# DCDC_12V_5V_3_3V.net
KiCad netlist of a schematic drawn in Altium Designer
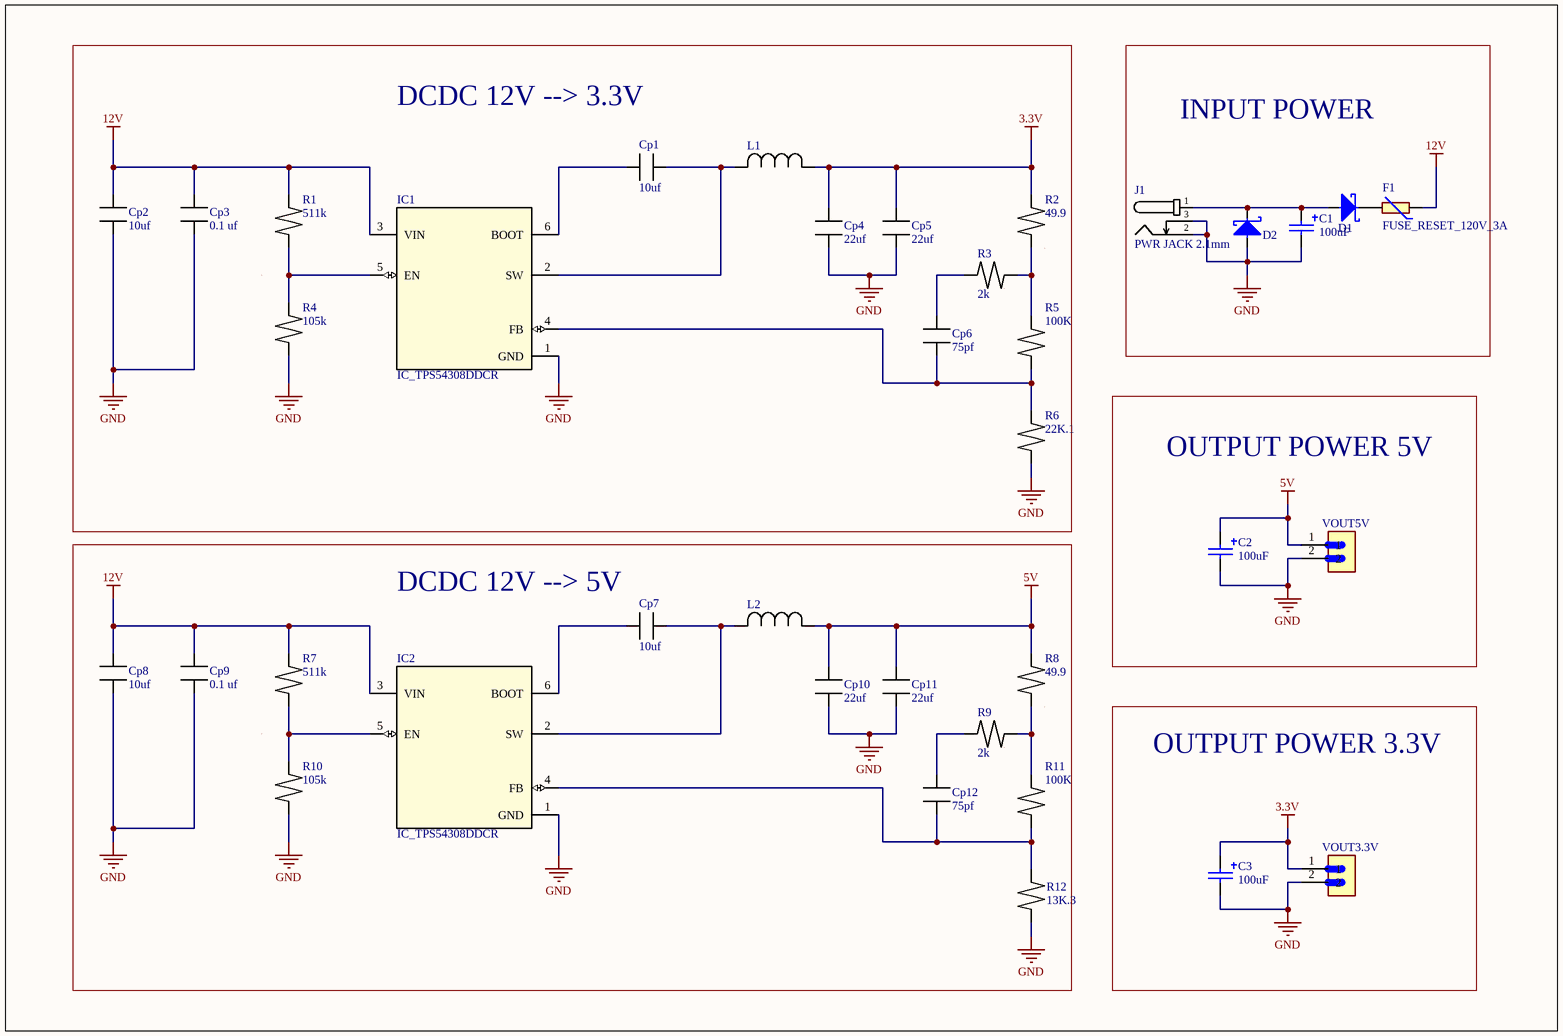
[diagram p0: DCDC_12V_5V_3.3V.SchDoc]

(export (version "E")
  (design (tool "Eeschema 10.0.6"))
  (components
    (comp (ref "C1")
      (value "100uF")
      (footprint "CAP_TH_2.5MM_6.3*12MM")
      (description "100uF 35V ±20% Plugin,D6.3xL12mm Aluminum Electrolytic Capacitors - Leaded ROHS")
      (fields (field (name "MANUFACTURER") "HRK") (field (name "MANUFACTURER PART NUMBER") "35V100uF CD110"))
      (libsource (lib "shared_lib") (part "Cap_100uF_ALU_TH_35V"))
    )
    (comp (ref "C2")
      (value "100uF")
      (footprint "CAP_TH_2.5MM_6.3*12MM")
      (description "100uF 35V ±20% Plugin,D6.3xL12mm Aluminum Electrolytic Capacitors - Leaded ROHS")
      (fields (field (name "MANUFACTURER") "HRK") (field (name "MANUFACTURER PART NUMBER") "35V100uF CD110"))
      (libsource (lib "shared_lib") (part "Cap_100uF_ALU_TH_35V"))
    )
    (comp (ref "C3")
      (value "100uF")
      (footprint "CAP_TH_2.5MM_6.3*12MM")
      (description "100uF 35V ±20% Plugin,D6.3xL12mm Aluminum Electrolytic Capacitors - Leaded ROHS")
      (fields (field (name "MANUFACTURER") "HRK") (field (name "MANUFACTURER PART NUMBER") "35V100uF CD110"))
      (libsource (lib "shared_lib") (part "Cap_100uF_ALU_TH_35V"))
    )
    (comp (ref "Cp1")
      (value "10uf")
      (footprint "Capacitor_0805")
      (description "CAP CER 10UF 50V X5R 0805")
      (fields (field (name "MANUFACTURER") "Murata Electronics") (field (name "Comment") "10uf 0805"))
      (libsource (lib "Schlib1") (part "Capacitor_10uf_0805_50V"))
    )
    (comp (ref "Cp2")
      (value "10uf")
      (footprint "Capacitor_0805")
      (description "CAP CER 10UF 50V X5R 0805")
      (fields (field (name "MANUFACTURER") "Murata Electronics") (field (name "Comment") "10uf 0805"))
      (libsource (lib "Schlib1") (part "Capacitor_10uf_0805_50V"))
    )
    (comp (ref "Cp3")
      (value "0.1 uf")
      (footprint "Capacitor_0603")
      (description "CAP CER 0.1UF 50V X7R 0603")
      (fields (field (name "MANUFACTURER") "KYOCERA AVX") (field (name "Comment") "0.1uf 0603"))
      (libsource (lib "Schlib1") (part "Capacitor_0.1uf_0603_50V"))
    )
    (comp (ref "Cp4")
      (value "22uf")
      (footprint "Capacitor_0805")
      (description "CAP0805 X5R 22UF 20% 25V")
      (fields (field (name "MANUFACTURER") "Cal-Chip Electronics, Inc.") (field (name "Comment") "22uf 0805"))
      (libsource (lib "Schlib1") (part "Capacitor_22uf_0805_50V_1"))
    )
    (comp (ref "Cp5")
      (value "22uf")
      (footprint "Capacitor_0805")
      (description "CAP0805 X5R 22UF 20% 25V")
      (fields (field (name "MANUFACTURER") "Cal-Chip Electronics, Inc.") (field (name "Comment") "22uf 0805"))
      (libsource (lib "Schlib1") (part "Capacitor_22uf_0805_50V_1"))
    )
    (comp (ref "Cp6")
      (value "75pf")
      (footprint "Capacitor_0805")
      (description "CAP CER 75PF 50V C0G/NPO 0805")
      (fields (field (name "MANUFACTURER") "YAGEO") (field (name "Comment") "75pf 0805"))
      (libsource (lib "Schlib1") (part "Capacitor_75pf_0805_50V"))
    )
    (comp (ref "Cp7")
      (value "10uf")
      (footprint "Capacitor_0805")
      (description "CAP CER 10UF 50V X5R 0805")
      (fields (field (name "MANUFACTURER") "Murata Electronics") (field (name "Comment") "10uf 0805"))
      (libsource (lib "Schlib1") (part "Capacitor_10uf_0805_50V"))
    )
    (comp (ref "Cp8")
      (value "10uf")
      (footprint "Capacitor_0805")
      (description "CAP CER 10UF 50V X5R 0805")
      (fields (field (name "MANUFACTURER") "Murata Electronics") (field (name "Comment") "10uf 0805"))
      (libsource (lib "Schlib1") (part "Capacitor_10uf_0805_50V"))
    )
    (comp (ref "Cp9")
      (value "0.1 uf")
      (footprint "Capacitor_0603")
      (description "CAP CER 0.1UF 50V X7R 0603")
      (fields (field (name "MANUFACTURER") "KYOCERA AVX") (field (name "Comment") "0.1uf 0603"))
      (libsource (lib "Schlib1") (part "Capacitor_0.1uf_0603_50V"))
    )
    (comp (ref "Cp10")
      (value "22uf")
      (footprint "Capacitor_0805")
      (description "CAP0805 X5R 22UF 20% 25V")
      (fields (field (name "MANUFACTURER") "Cal-Chip Electronics, Inc.") (field (name "Comment") "22uf 0805"))
      (libsource (lib "Schlib1") (part "Capacitor_22uf_0805_50V_1"))
    )
    (comp (ref "Cp11")
      (value "22uf")
      (footprint "Capacitor_0805")
      (description "CAP0805 X5R 22UF 20% 25V")
      (fields (field (name "MANUFACTURER") "Cal-Chip Electronics, Inc.") (field (name "Comment") "22uf 0805"))
      (libsource (lib "Schlib1") (part "Capacitor_22uf_0805_50V_1"))
    )
    (comp (ref "Cp12")
      (value "75pf")
      (footprint "Capacitor_0805")
      (description "CAP CER 75PF 50V C0G/NPO 0805")
      (fields (field (name "MANUFACTURER") "YAGEO") (field (name "Comment") "75pf 0805"))
      (libsource (lib "Schlib1") (part "Capacitor_75pf_0805_50V"))
    )
    (comp (ref "D1")
      (value "30V 3A")
      (footprint "SMA")
      (description "40V Independent 3A 550mV@3A SMA Schottky Diodes ROHS")
      (fields (field (name "MANUFACTURER") "TDSEMIC") (field (name "MANUFACTURER PART NUMBER") "SS34-TD"))
      (libsource (lib "shared_lib") (part "D_Schottky_40V_3A_SMA"))
    )
    (comp (ref "D2")
      (value "30V 3A")
      (footprint "SMA")
      (description "40V Independent 3A 550mV@3A SMA Schottky Diodes ROHS")
      (fields (field (name "MANUFACTURER") "TDSEMIC") (field (name "MANUFACTURER PART NUMBER") "SS34-TD"))
      (libsource (lib "shared_lib") (part "D_Schottky_40V_3A_SMA"))
    )
    (comp (ref "F1")
      (value "FUSE_RESET_120V_3A")
      (footprint "FUS_RES_120V_3A")
      (description "PTC RESET FUSE 120V 300MA RADIAL")
      (fields (field (name "MANUFACTURER") "Bel Fuse Inc."))
      (libsource (lib "Schlib1") (part "FUSE_RESET_120V_3A"))
    )
    (comp (ref "IC1")
      (value "IC_TPS54308DDCR")
      (footprint "IC_TPS54308DDCR")
      (description "IC REG BUCK ADJ 3A SOT23")
      (fields (field (name "MANUFACTURER") "Texas Instruments"))
      (libsource (lib "Schlib1") (part "IC_TPS54308DDCR"))
    )
    (comp (ref "IC2")
      (value "IC_TPS54308DDCR")
      (footprint "IC_TPS54308DDCR")
      (description "IC REG BUCK ADJ 3A SOT23")
      (fields (field (name "MANUFACTURER") "Texas Instruments"))
      (libsource (lib "Schlib1") (part "IC_TPS54308DDCR"))
    )
    (comp (ref "J1")
      (value "PWR JACK 2.1mm")
      (footprint "CON_POWER_BARREL_2.1MM_3CONN")
      (description "CONN PWR JACK 2X5.5MM SOLDER")
      (fields (field (name "MANUFACTURER") "HCTL") (field (name "MANUFACTURER PART NUMBER") "HC-DC-005-2.0T"))
      (libsource (lib "shared_lib") (part "Con_Power_Jack_2.1mm_3pins"))
    )
    (comp (ref "L1")
      (value "IND 10UH 3.1A")
      (footprint "Inductor_10uh_3.1A")
      (description "FIXED IND 10UH 3.1A 44.2 MOHM")
      (fields (field (name "MANUFACTURER") "Taiyo Yuden"))
      (libsource (lib "Schlib1") (part "IND_10UH_3.1A"))
    )
    (comp (ref "L2")
      (value "IND 15UH 3.1A")
      (footprint "Inductor_10uh_3.1A")
      (description "FIXED IND 15UH 3.1A 44 MOHM SMD")
      (fields (field (name "MANUFACTURER") "Eaton - Electronics Division"))
      (libsource (lib "Schlib1") (part "IND_15UH_3.1A"))
    )
    (comp (ref "R1")
      (value "511k")
      (footprint "0603_resistor")
      (description "RES 511K OHM 1% 1/10W 0603")
      (fields (field (name "MANUFACTURER") "Cal-Chip Electronics, Inc.") (field (name "Comment") "511K 0603"))
      (libsource (lib "Schlib1") (part "RES_511K_0603_1/10W_1%_1_1_1"))
    )
    (comp (ref "R2")
      (value "49.9")
      (footprint "0603_resistor")
      (description "RES 49.9 OHM 1% 1/10W 0603")
      (fields (field (name "MANUFACTURER") "YAGEO") (field (name "Comment") "49.9 0603"))
      (libsource (lib "Schlib1") (part "RES_49.9_0603_1/10W_1%"))
    )
    (comp (ref "R3")
      (value "2k")
      (footprint "0603_resistor")
      (description "RES 2K OHM 1% 1/10W 0603")
      (fields (field (name "MANUFACTURER") "NIC Components Corp") (field (name "Comment") "2K 0603"))
      (libsource (lib "Schlib1") (part "RES_2K_0603_1/10W_1%_1"))
    )
    (comp (ref "R4")
      (value "105k")
      (footprint "0603_resistor")
      (description "RES 105K OHM 1% 1/10W 0603")
      (fields (field (name "MANUFACTURER") "Cal-Chip Electronics, Inc.") (field (name "Comment") "105K 0603"))
      (libsource (lib "Schlib1") (part "RES_105K_0603_1/10W_1%_1_1"))
    )
    (comp (ref "R5")
      (value "100K")
      (footprint "0603_resistor")
      (description "RES 100K OHM 1% 1/10W 0603")
      (fields (field (name "MANUFACTURER") "YAGEO") (field (name "Comment") "100K 0603"))
      (libsource (lib "Schlib1") (part "RES_100K_0603_1/10W_1%_1"))
    )
    (comp (ref "R6")
      (value "22K.1")
      (footprint "0603_resistor")
      (description "RES 22K.1 OHM 1% 1/10W 0603")
      (fields (field (name "MANUFACTURER") "YAGEO") (field (name "Comment") "22K.1 0603"))
      (libsource (lib "Schlib1") (part "RES_22K.1_0603_1/10W_1%_1_1"))
    )
    (comp (ref "R7")
      (value "511k")
      (footprint "0603_resistor")
      (description "RES 511K OHM 1% 1/10W 0603")
      (fields (field (name "MANUFACTURER") "Cal-Chip Electronics, Inc.") (field (name "Comment") "511K 0603"))
      (libsource (lib "Schlib1") (part "RES_511K_0603_1/10W_1%_1_1_1"))
    )
    (comp (ref "R8")
      (value "49.9")
      (footprint "0603_resistor")
      (description "RES 49.9 OHM 1% 1/10W 0603")
      (fields (field (name "MANUFACTURER") "YAGEO") (field (name "Comment") "49.9 0603"))
      (libsource (lib "Schlib1") (part "RES_49.9_0603_1/10W_1%"))
    )
    (comp (ref "R9")
      (value "2k")
      (footprint "0603_resistor")
      (description "RES 2K OHM 1% 1/10W 0603")
      (fields (field (name "MANUFACTURER") "NIC Components Corp") (field (name "Comment") "2K 0603"))
      (libsource (lib "Schlib1") (part "RES_2K_0603_1/10W_1%_1"))
    )
    (comp (ref "R10")
      (value "105k")
      (footprint "0603_resistor")
      (description "RES 105K OHM 1% 1/10W 0603")
      (fields (field (name "MANUFACTURER") "Cal-Chip Electronics, Inc.") (field (name "Comment") "105K 0603"))
      (libsource (lib "Schlib1") (part "RES_105K_0603_1/10W_1%_1_1"))
    )
    (comp (ref "R11")
      (value "100K")
      (footprint "0603_resistor")
      (description "RES 100K OHM 1% 1/10W 0603")
      (fields (field (name "MANUFACTURER") "YAGEO") (field (name "Comment") "100K 0603"))
      (libsource (lib "Schlib1") (part "RES_100K_0603_1/10W_1%_1"))
    )
    (comp (ref "R12")
      (value "13K.3")
      (footprint "0603_resistor")
      (description "RES 13.3K OHM 1% 1/10W 0603")
      (fields (field (name "MANUFACTURER") "Stackpole Electronics Inc") (field (name "Comment") "13K.3 0603"))
      (libsource (lib "Schlib1") (part "RES_13K.3_0603_1/10W_1%_"))
    )
    (comp (ref "VOUT3.3V")
      (value "TERM BLK 2POS")
      (footprint "TERM_BLK_2POS")
      (description "TERM BLK 2POS SIDE ENT 3.5MM PCB")
      (fields (field (name "MANUFACTURER") "On Shore Technology Inc."))
      (libsource (lib "Schlib1") (part "TERM_BLK_2POS"))
    )
    (comp (ref "VOUT5V")
      (value "TERM BLK 2POS")
      (footprint "TERM_BLK_2POS")
      (description "TERM BLK 2POS SIDE ENT 3.5MM PCB")
      (fields (field (name "MANUFACTURER") "On Shore Technology Inc."))
      (libsource (lib "Schlib1") (part "TERM_BLK_2POS"))
    )
  )
  (nets
    (net (code "1") (name "3.3V") (class "Default")
      (node (ref "C3") (pin "1") (pinfunction "1_1") (pintype "passive"))
      (node (ref "Cp4") (pin "2") (pinfunction "-_2") (pintype "passive"))
      (node (ref "Cp5") (pin "2") (pinfunction "-_2") (pintype "passive"))
      (node (ref "L1") (pin "1") (pinfunction "1_1") (pintype "passive"))
      (node (ref "R2") (pin "2") (pintype "passive"))
      (node (ref "VOUT3.3V") (pin "1") (pinfunction "1_1") (pintype "passive"))
    )
    (net (code "2") (name "5V") (class "Default")
      (node (ref "C2") (pin "1") (pinfunction "1_1") (pintype "passive"))
      (node (ref "Cp10") (pin "2") (pinfunction "-_2") (pintype "passive"))
      (node (ref "Cp11") (pin "2") (pinfunction "-_2") (pintype "passive"))
      (node (ref "L2") (pin "1") (pinfunction "1_1") (pintype "passive"))
      (node (ref "R8") (pin "2") (pintype "passive"))
      (node (ref "VOUT5V") (pin "1") (pinfunction "1_1") (pintype "passive"))
    )
    (net (code "3") (name "12V") (class "Default")
      (node (ref "Cp2") (pin "2") (pinfunction "-_2") (pintype "passive"))
      (node (ref "Cp3") (pin "2") (pinfunction "-_2") (pintype "passive"))
      (node (ref "Cp8") (pin "2") (pinfunction "-_2") (pintype "passive"))
      (node (ref "Cp9") (pin "2") (pinfunction "-_2") (pintype "passive"))
      (node (ref "F1") (pin "1") (pinfunction "1_1") (pintype "passive"))
      (node (ref "IC1") (pin "3") (pinfunction "VIN_3") (pintype "power_in"))
      (node (ref "IC2") (pin "3") (pinfunction "VIN_3") (pintype "power_in"))
      (node (ref "R1") (pin "2") (pintype "passive"))
      (node (ref "R7") (pin "2") (pintype "passive"))
    )
    (net (code "4") (name "GND") (class "Default")
      (node (ref "C1") (pin "2") (pinfunction "2_2") (pintype "passive"))
      (node (ref "C2") (pin "2") (pinfunction "2_2") (pintype "passive"))
      (node (ref "C3") (pin "2") (pinfunction "2_2") (pintype "passive"))
      (node (ref "Cp10") (pin "1") (pinfunction "+_1") (pintype "passive"))
      (node (ref "Cp11") (pin "1") (pinfunction "+_1") (pintype "passive"))
      (node (ref "Cp2") (pin "1") (pinfunction "+_1") (pintype "passive"))
      (node (ref "Cp3") (pin "1") (pinfunction "+_1") (pintype "passive"))
      (node (ref "Cp4") (pin "1") (pinfunction "+_1") (pintype "passive"))
      (node (ref "Cp5") (pin "1") (pinfunction "+_1") (pintype "passive"))
      (node (ref "Cp8") (pin "1") (pinfunction "+_1") (pintype "passive"))
      (node (ref "Cp9") (pin "1") (pinfunction "+_1") (pintype "passive"))
      (node (ref "D2") (pin "2") (pinfunction "2_2") (pintype "passive"))
      (node (ref "IC1") (pin "1") (pinfunction "GND_1") (pintype "power_in"))
      (node (ref "IC2") (pin "1") (pinfunction "GND_1") (pintype "power_in"))
      (node (ref "J1") (pin "2") (pinfunction "2_2") (pintype "passive"))
      (node (ref "J1") (pin "3") (pinfunction "3_3") (pintype "passive"))
      (node (ref "R10") (pin "1") (pintype "passive"))
      (node (ref "R12") (pin "1") (pintype "passive"))
      (node (ref "R4") (pin "1") (pintype "passive"))
      (node (ref "R6") (pin "1") (pintype "passive"))
      (node (ref "VOUT3.3V") (pin "2") (pinfunction "2_2") (pintype "passive"))
      (node (ref "VOUT5V") (pin "2") (pinfunction "2_2") (pintype "passive"))
    )
    (net (code "5") (name "Net-(C1-Pad1)") (class "Default")
      (node (ref "C1") (pin "1") (pinfunction "1_1") (pintype "passive"))
      (node (ref "D1") (pin "2") (pinfunction "2_2") (pintype "passive"))
      (node (ref "D2") (pin "1") (pinfunction "1_1") (pintype "passive"))
      (node (ref "J1") (pin "1") (pinfunction "1_1") (pintype "passive"))
    )
    (net (code "6") (name "Net-(Cp1-+)") (class "Default")
      (node (ref "Cp1") (pin "1") (pinfunction "+_1") (pintype "passive"))
      (node (ref "IC1") (pin "6") (pinfunction "BOOT_6") (pintype "power_in"))
    )
    (net (code "7") (name "Net-(Cp1--)") (class "Default")
      (node (ref "Cp1") (pin "2") (pinfunction "-_2") (pintype "passive"))
      (node (ref "IC1") (pin "2") (pinfunction "SW_2") (pintype "power_in"))
      (node (ref "L1") (pin "2") (pinfunction "2_2") (pintype "passive"))
    )
    (net (code "8") (name "Net-(Cp6-+)") (class "Default")
      (node (ref "Cp6") (pin "1") (pinfunction "+_1") (pintype "passive"))
      (node (ref "IC1") (pin "4") (pinfunction "FB_4") (pintype "bidirectional"))
      (node (ref "R5") (pin "1") (pintype "passive"))
      (node (ref "R6") (pin "2") (pintype "passive"))
    )
    (net (code "9") (name "Net-(Cp6--)") (class "Default")
      (node (ref "Cp6") (pin "2") (pinfunction "-_2") (pintype "passive"))
      (node (ref "R3") (pin "1") (pintype "passive"))
    )
    (net (code "10") (name "Net-(Cp7-+)") (class "Default")
      (node (ref "Cp7") (pin "1") (pinfunction "+_1") (pintype "passive"))
      (node (ref "IC2") (pin "6") (pinfunction "BOOT_6") (pintype "power_in"))
    )
    (net (code "11") (name "Net-(Cp7--)") (class "Default")
      (node (ref "Cp7") (pin "2") (pinfunction "-_2") (pintype "passive"))
      (node (ref "IC2") (pin "2") (pinfunction "SW_2") (pintype "power_in"))
      (node (ref "L2") (pin "2") (pinfunction "2_2") (pintype "passive"))
    )
    (net (code "12") (name "Net-(Cp12-+)") (class "Default")
      (node (ref "Cp12") (pin "1") (pinfunction "+_1") (pintype "passive"))
      (node (ref "IC2") (pin "4") (pinfunction "FB_4") (pintype "bidirectional"))
      (node (ref "R11") (pin "1") (pintype "passive"))
      (node (ref "R12") (pin "2") (pintype "passive"))
    )
    (net (code "13") (name "Net-(Cp12--)") (class "Default")
      (node (ref "Cp12") (pin "2") (pinfunction "-_2") (pintype "passive"))
      (node (ref "R9") (pin "1") (pintype "passive"))
    )
    (net (code "14") (name "Net-(D1-Pad1)") (class "Default")
      (node (ref "D1") (pin "1") (pinfunction "1_1") (pintype "passive"))
      (node (ref "F1") (pin "2") (pinfunction "2_2") (pintype "passive"))
    )
    (net (code "15") (name "Net-(IC1-EN)") (class "Default")
      (node (ref "IC1") (pin "5") (pinfunction "EN_5") (pintype "bidirectional"))
      (node (ref "R1") (pin "1") (pintype "passive"))
      (node (ref "R4") (pin "2") (pintype "passive"))
    )
    (net (code "16") (name "Net-(IC2-EN)") (class "Default")
      (node (ref "IC2") (pin "5") (pinfunction "EN_5") (pintype "bidirectional"))
      (node (ref "R10") (pin "2") (pintype "passive"))
      (node (ref "R7") (pin "1") (pintype "passive"))
    )
    (net (code "17") (name "Net-(R2-Pad1)") (class "Default")
      (node (ref "R2") (pin "1") (pintype "passive"))
      (node (ref "R3") (pin "2") (pintype "passive"))
      (node (ref "R5") (pin "2") (pintype "passive"))
    )
    (net (code "18") (name "Net-(R11-Pad2)") (class "Default")
      (node (ref "R11") (pin "2") (pintype "passive"))
      (node (ref "R8") (pin "1") (pintype "passive"))
      (node (ref "R9") (pin "2") (pintype "passive"))
    )
  )
)
